# Periph.net
KiCad netlist of a schematic drawn in Altium Designer
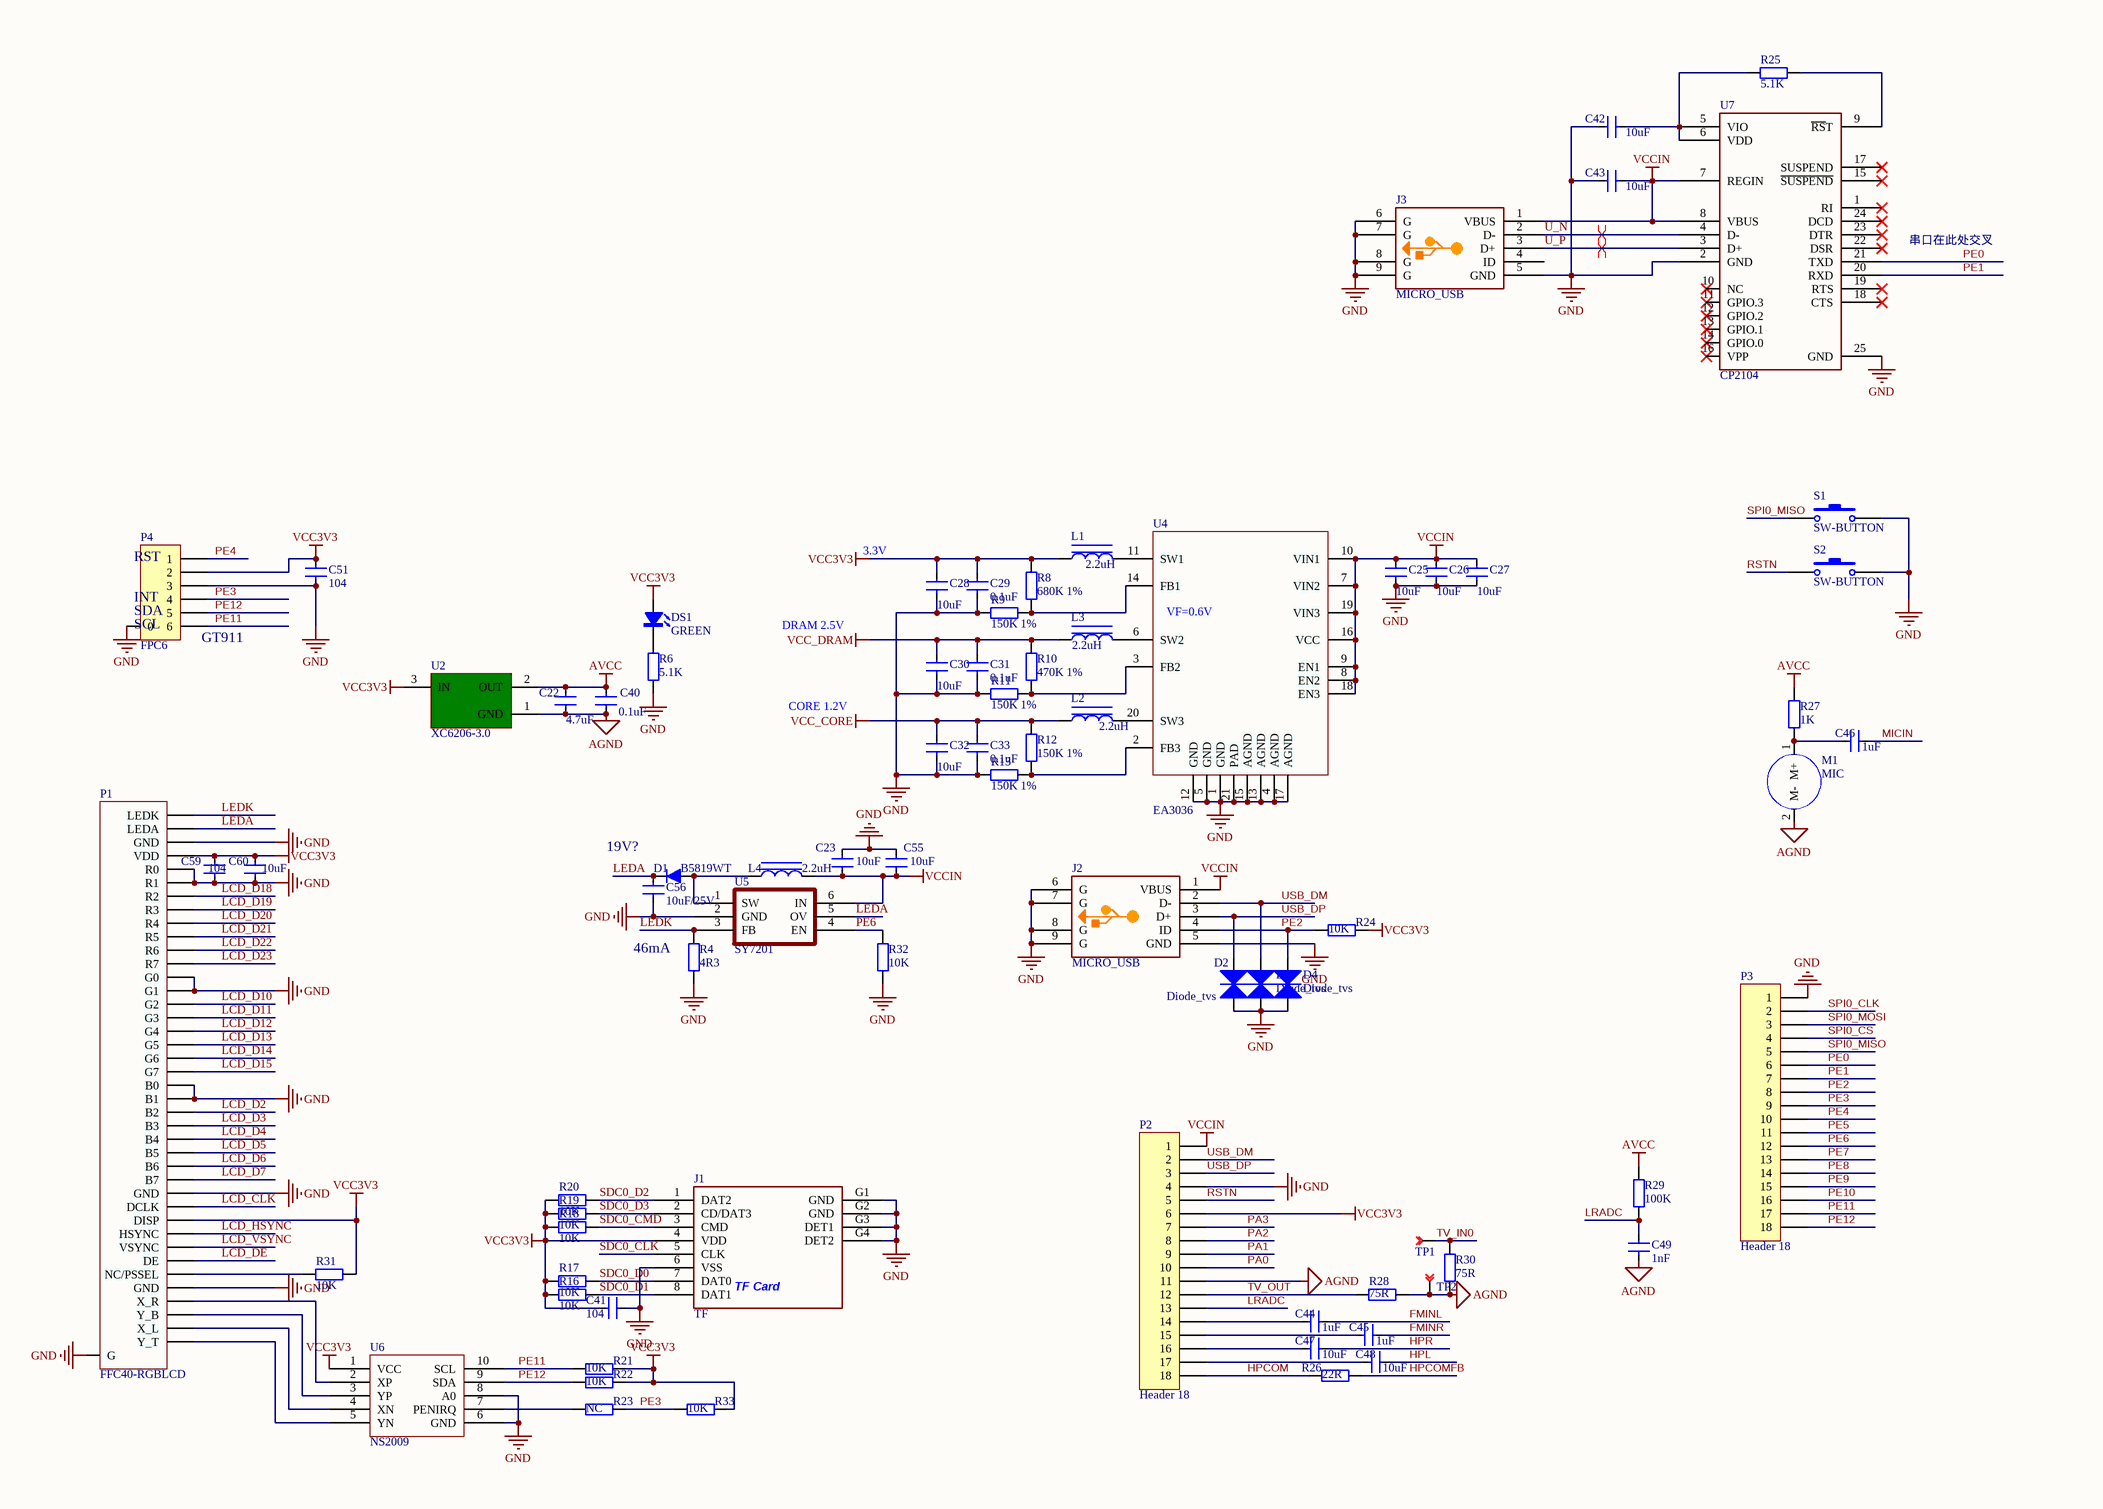
[diagram p0: Periph.SchDoc]

(export (version "E")
  (design (tool "Eeschema 10.0.6"))
  (components
    (comp (ref "C22")
      (value "4.7uF")
      (footprint "C0402")
      (description "普通小电容")
      (libsource (lib "LIB_MANGO") (part "CAP"))
    )
    (comp (ref "C23")
      (value "10uF")
      (footprint "C0402")
      (description "普通小电容")
      (libsource (lib "LIB_MANGO") (part "CAP"))
    )
    (comp (ref "C25")
      (value "10uF")
      (footprint "C0402")
      (description "普通小电容")
      (libsource (lib "LIB_MANGO") (part "CAP"))
    )
    (comp (ref "C26")
      (value "10uF")
      (footprint "C0402")
      (description "普通小电容")
      (libsource (lib "LIB_MANGO") (part "CAP"))
    )
    (comp (ref "C27")
      (value "10uF")
      (footprint "C0402")
      (description "普通小电容")
      (libsource (lib "LIB_MANGO") (part "CAP"))
    )
    (comp (ref "C28")
      (value "10uF")
      (footprint "C0402")
      (description "普通小电容")
      (libsource (lib "LIB_MANGO") (part "CAP"))
    )
    (comp (ref "C29")
      (value "0.1uF")
      (footprint "C0402")
      (description "普通小电容")
      (libsource (lib "LIB_MANGO") (part "CAP"))
    )
    (comp (ref "C30")
      (value "10uF")
      (footprint "C0402")
      (description "普通小电容")
      (libsource (lib "LIB_MANGO") (part "CAP"))
    )
    (comp (ref "C31")
      (value "0.1uF")
      (footprint "C0402")
      (description "普通小电容")
      (libsource (lib "LIB_MANGO") (part "CAP"))
    )
    (comp (ref "C32")
      (value "10uF")
      (footprint "C0402")
      (description "普通小电容")
      (libsource (lib "LIB_MANGO") (part "CAP"))
    )
    (comp (ref "C33")
      (value "0.1uF")
      (footprint "C0402")
      (description "普通小电容")
      (libsource (lib "LIB_MANGO") (part "CAP"))
    )
    (comp (ref "C40")
      (value "0.1uF")
      (footprint "C0402")
      (description "普通小电容")
      (libsource (lib "LIB_MANGO") (part "CAP"))
    )
    (comp (ref "C41")
      (value "104")
      (footprint "C0402")
      (description "普通小电容")
      (libsource (lib "LIB_MANGO") (part "CAP"))
    )
    (comp (ref "C42")
      (value "10uF")
      (footprint "C0402")
      (description "普通小电容")
      (libsource (lib "LIB_MANGO") (part "CAP"))
    )
    (comp (ref "C43")
      (value "10uF")
      (footprint "C0402")
      (description "普通小电容")
      (libsource (lib "LIB_MANGO") (part "CAP"))
    )
    (comp (ref "C44")
      (value "1uF")
      (footprint "C0402")
      (description "普通小电容")
      (libsource (lib "LIB_MANGO") (part "CAP"))
    )
    (comp (ref "C45")
      (value "1uF")
      (footprint "C0402")
      (description "普通小电容")
      (libsource (lib "LIB_MANGO") (part "CAP"))
    )
    (comp (ref "C46")
      (value "1uF")
      (footprint "C0402")
      (description "普通小电容")
      (libsource (lib "LIB_MANGO") (part "CAP"))
    )
    (comp (ref "C47")
      (value "10uF")
      (footprint "C0402")
      (description "普通小电容")
      (libsource (lib "LIB_MANGO") (part "CAP"))
    )
    (comp (ref "C48")
      (value "10uF")
      (footprint "C0402")
      (description "普通小电容")
      (libsource (lib "LIB_MANGO") (part "CAP"))
    )
    (comp (ref "C49")
      (value "1nF")
      (footprint "C0402")
      (description "普通小电容")
      (libsource (lib "LIB_MANGO") (part "CAP"))
    )
    (comp (ref "C51")
      (value "104")
      (footprint "C0402")
      (description "普通小电容")
      (libsource (lib "LIB_MANGO") (part "CAP"))
    )
    (comp (ref "C55")
      (value "10uF")
      (footprint "C0402")
      (description "普通小电容")
      (libsource (lib "LIB_MANGO") (part "CAP"))
    )
    (comp (ref "C56")
      (value "10uF/25V")
      (footprint "C0603")
      (description "普通小电容")
      (libsource (lib "LIB_MANGO") (part "CAP"))
    )
    (comp (ref "C59")
      (value "104")
      (footprint "C0402")
      (description "普通小电容")
      (libsource (lib "LIB_MANGO") (part "CAP"))
    )
    (comp (ref "C60")
      (value "10uF")
      (footprint "C0402")
      (description "普通小电容")
      (libsource (lib "LIB_MANGO") (part "CAP"))
    )
    (comp (ref "D1")
      (value "B5819WT")
      (footprint "SOD523")
      (description "普通二极管")
      (libsource (lib "A") (part "Diode"))
    )
    (comp (ref "D2")
      (value "Diode_tvs")
      (footprint "0402TVS")
      (description "tvs")
      (libsource (lib "LIB_MANGO") (part "Diode_tvs"))
    )
    (comp (ref "D3")
      (value "Diode_tvs")
      (footprint "0402TVS")
      (description "tvs")
      (libsource (lib "LIB_MANGO") (part "Diode_tvs"))
    )
    (comp (ref "D4")
      (value "Diode_tvs")
      (footprint "0402TVS")
      (description "tvs")
      (libsource (lib "LIB_MANGO") (part "Diode_tvs"))
    )
    (comp (ref "DS1") (value "GREEN") (footprint "LED0402") (libsource (lib "A") (part "LED")))
    (comp (ref "J1")
      (value "TF")
      (footprint "TFCARD473092651")
      (libsource (lib "LIB_MANGO") (part "TF_473092651"))
    )
    (comp (ref "J2")
      (value "MICRO_USB")
      (footprint "MICROUSB")
      (libsource (lib "LIB_MANGO") (part "MICRO_USB"))
    )
    (comp (ref "J3")
      (value "MICRO_USB")
      (footprint "MICROUSB")
      (libsource (lib "LIB_MANGO") (part "MICRO_USB"))
    )
    (comp (ref "L1")
      (value "2.2uH")
      (footprint "VLS2016")
      (description "普通电感")
      (libsource (lib "LIB_MANGO") (part "L"))
    )
    (comp (ref "L2")
      (value "2.2uH")
      (footprint "VLS2016")
      (description "普通电感")
      (libsource (lib "LIB_MANGO") (part "L"))
    )
    (comp (ref "L3")
      (value "2.2uH")
      (footprint "VLS2016")
      (description "普通电感")
      (libsource (lib "A") (part "L"))
    )
    (comp (ref "L4")
      (value "2.2uH")
      (footprint "VLS3012E")
      (description "普通电感")
      (libsource (lib "LIB_MANGO") (part "L"))
    )
    (comp (ref "M1") (value "MIC") (footprint "MIC") (libsource (lib "LIB_MANGO") (part "MIC")))
    (comp (ref "P1")
      (value "FFC40-RGBLCD")
      (footprint "FFC/SM0.5-1H40")
      (fields (field (name "PUBLISHER") "Altium Limited"))
      (libsource (lib "LIB_MANGO") (part "FFC40-RGBLCD"))
    )
    (comp (ref "P2")
      (value "Header 18")
      (footprint "HDR1X18-M2")
      (description "Header, 18-Pin")
      (fields (field (name "PUBLISHER") "Altium Limited"))
      (libsource (lib "LIB_MANGO") (part "Header 18"))
    )
    (comp (ref "P3")
      (value "Header 18")
      (footprint "HDR1X18-M2")
      (description "Header, 18-Pin")
      (fields (field (name "PUBLISHER") "Altium Limited"))
      (libsource (lib "LIB_MANGO") (part "Header 18"))
    )
    (comp (ref "P4")
      (value "FPC6")
      (footprint "FPC6")
      (fields (field (name "PUBLISHER") "Altium Limited"))
      (libsource (lib "LIB_MANGO") (part "FPC6"))
    )
    (comp (ref "R4")
      (value "4R3")
      (footprint "R0402")
      (description "普通电阻")
      (libsource (lib "") (part "RES_2"))
    )
    (comp (ref "R6")
      (value "5.1K")
      (footprint "R0402")
      (description "普通电阻1%精度")
      (libsource (lib "") (part "RES_1"))
    )
    (comp (ref "R8")
      (value "680K 1%")
      (footprint "R0402")
      (description "普通电阻")
      (libsource (lib "") (part "RES_1"))
    )
    (comp (ref "R9")
      (value "150K 1%")
      (footprint "R0402")
      (description "普通电阻")
      (libsource (lib "") (part "RES_3"))
    )
    (comp (ref "R10")
      (value "470K 1%")
      (footprint "R0402")
      (description "普通电阻")
      (libsource (lib "") (part "RES_1"))
    )
    (comp (ref "R11")
      (value "150K 1%")
      (footprint "R0402")
      (description "普通电阻")
      (libsource (lib "") (part "RES_3"))
    )
    (comp (ref "R12")
      (value "150K 1%")
      (footprint "R0402")
      (description "普通电阻")
      (libsource (lib "") (part "RES_1"))
    )
    (comp (ref "R13")
      (value "150K 1%")
      (footprint "R0402")
      (description "普通电阻")
      (libsource (lib "") (part "RES_3"))
    )
    (comp (ref "R16")
      (value "10K")
      (footprint "R0402")
      (description "普通电阻")
      (libsource (lib "") (part "RES_2"))
    )
    (comp (ref "R17")
      (value "10K")
      (footprint "R0402")
      (description "普通电阻")
      (libsource (lib "") (part "RES_2"))
    )
    (comp (ref "R18")
      (value "10K")
      (footprint "R0402")
      (description "普通电阻")
      (libsource (lib "") (part "RES_2"))
    )
    (comp (ref "R19")
      (value "10K")
      (footprint "R0402")
      (description "普通电阻")
      (libsource (lib "") (part "RES_2"))
    )
    (comp (ref "R20")
      (value "10K")
      (footprint "R0402")
      (description "普通电阻")
      (libsource (lib "") (part "RES_2"))
    )
    (comp (ref "R21")
      (value "10K")
      (footprint "R0402")
      (description "普通电阻")
      (libsource (lib "LIB_MANGO") (part "RES"))
    )
    (comp (ref "R22")
      (value "10K")
      (footprint "R0402")
      (description "普通电阻")
      (libsource (lib "LIB_MANGO") (part "RES"))
    )
    (comp (ref "R23")
      (value "NC")
      (footprint "R0402")
      (description "普通电阻")
      (libsource (lib "") (part "RES_2"))
    )
    (comp (ref "R24")
      (value "10K")
      (footprint "R0402")
      (description "普通电阻")
      (libsource (lib "LIB_MANGO") (part "RES"))
    )
    (comp (ref "R25")
      (value "5.1K")
      (footprint "R0402")
      (description "普通电阻")
      (libsource (lib "LIB_MANGO") (part "RES"))
    )
    (comp (ref "R26")
      (value "22R")
      (footprint "R0402")
      (description "普通电阻")
      (libsource (lib "LIB_MANGO") (part "RES"))
    )
    (comp (ref "R27")
      (value "1K")
      (footprint "R0402")
      (description "普通电阻")
      (libsource (lib "") (part "RES_1"))
    )
    (comp (ref "R28")
      (value "75R")
      (footprint "R0402")
      (description "普通电阻")
      (libsource (lib "LIB_MANGO") (part "RES"))
    )
    (comp (ref "R29")
      (value "100K")
      (footprint "R0402")
      (description "普通电阻")
      (libsource (lib "") (part "RES_2"))
    )
    (comp (ref "R30")
      (value "75R")
      (footprint "R0402")
      (description "普通电阻")
      (libsource (lib "") (part "RES_1"))
    )
    (comp (ref "R31")
      (value "10K")
      (footprint "R0402")
      (description "普通电阻")
      (libsource (lib "") (part "RES_3"))
    )
    (comp (ref "R32")
      (value "10K")
      (footprint "R0402")
      (description "普通电阻")
      (libsource (lib "") (part "RES_1"))
    )
    (comp (ref "R33")
      (value "10K")
      (footprint "R0402")
      (description "普通电阻")
      (libsource (lib "LIB_MANGO") (part "RES"))
    )
    (comp (ref "S1")
      (value "SW-BUTTON")
      (footprint "MINIBUTTON")
      (libsource (lib "LIB_MANGO") (part "SW-BUTTON"))
    )
    (comp (ref "S2")
      (value "SW-BUTTON")
      (footprint "MINIBUTTON")
      (libsource (lib "LIB_MANGO") (part "SW-BUTTON"))
    )
    (comp (ref "TP1")
      (value "TEST POINT")
      (footprint "TEST-POINT")
      (description "Description")
      (libsource (lib "LIB_MANGO") (part "TP"))
    )
    (comp (ref "TP2")
      (value "TEST POINT")
      (footprint "TEST-POINT")
      (description "Description")
      (libsource (lib "LIB_MANGO") (part "TP"))
    )
    (comp (ref "U2") (value "XC6206-3.0") (footprint "SOT23") (libsource (lib "LIB_MANGO") (part "XC6206")))
    (comp (ref "U4")
      (value "EA3036")
      (footprint "QFN40P300X300X80_HS-21N")
      (libsource (lib "LIB_MANGO") (part "EA3036"))
    )
    (comp (ref "U5") (value "SY7201") (footprint "SOT23-6") (libsource (lib "LIB_MANGO") (part "PT4101")))
    (comp (ref "U6") (value "NS2009") (footprint "TSSOP10") (libsource (lib "LIB_MANGO") (part "NS2009")))
    (comp (ref "U7") (value "CP2104") (footprint "QFN24") (libsource (lib "LIB_MANGO") (part "CP2104")))
  )
  (nets
    (net (code "1") (name "/FMINL") (class "Default")
      (node (ref "C44") (pin "2") (pinfunction "2_2") (pintype "passive"))
    )
    (net (code "2") (name "/FMINR") (class "Default")
      (node (ref "C45") (pin "2") (pinfunction "2_2") (pintype "passive"))
    )
    (net (code "3") (name "/HPCOM") (class "Default")
      (node (ref "P2") (pin "18") (pinfunction "18_18") (pintype "passive"))
      (node (ref "R26") (pin "1") (pinfunction "1_1") (pintype "passive"))
    )
    (net (code "4") (name "/HPCOMFB") (class "Default")
      (node (ref "R26") (pin "2") (pinfunction "2_2") (pintype "passive"))
    )
    (net (code "5") (name "/HPL") (class "Default")
      (node (ref "C48") (pin "2") (pinfunction "2_2") (pintype "passive"))
    )
    (net (code "6") (name "/HPR") (class "Default")
      (node (ref "C47") (pin "2") (pinfunction "2_2") (pintype "passive"))
    )
    (net (code "7") (name "/LCD_CLK") (class "Default")
      (node (ref "P1") (pin "30") (pinfunction "DCLK_30") (pintype "passive"))
    )
    (net (code "8") (name "/LCD_D2") (class "Default")
      (node (ref "P1") (pin "23") (pinfunction "B2_23") (pintype "passive"))
    )
    (net (code "9") (name "/LCD_D3") (class "Default")
      (node (ref "P1") (pin "24") (pinfunction "B3_24") (pintype "passive"))
    )
    (net (code "10") (name "/LCD_D4") (class "Default")
      (node (ref "P1") (pin "25") (pinfunction "B4_25") (pintype "passive"))
    )
    (net (code "11") (name "/LCD_D5") (class "Default")
      (node (ref "P1") (pin "26") (pinfunction "B5_26") (pintype "passive"))
    )
    (net (code "12") (name "/LCD_D6") (class "Default")
      (node (ref "P1") (pin "27") (pinfunction "B6_27") (pintype "passive"))
    )
    (net (code "13") (name "/LCD_D7") (class "Default")
      (node (ref "P1") (pin "28") (pinfunction "B7_28") (pintype "passive"))
    )
    (net (code "14") (name "/LCD_D10") (class "Default")
      (node (ref "P1") (pin "15") (pinfunction "G2_15") (pintype "passive"))
    )
    (net (code "15") (name "/LCD_D11") (class "Default")
      (node (ref "P1") (pin "16") (pinfunction "G3_16") (pintype "passive"))
    )
    (net (code "16") (name "/LCD_D12") (class "Default")
      (node (ref "P1") (pin "17") (pinfunction "G4_17") (pintype "passive"))
    )
    (net (code "17") (name "/LCD_D13") (class "Default")
      (node (ref "P1") (pin "18") (pinfunction "G5_18") (pintype "passive"))
    )
    (net (code "18") (name "/LCD_D14") (class "Default")
      (node (ref "P1") (pin "19") (pinfunction "G6_19") (pintype "passive"))
    )
    (net (code "19") (name "/LCD_D15") (class "Default")
      (node (ref "P1") (pin "20") (pinfunction "G7_20") (pintype "passive"))
    )
    (net (code "20") (name "/LCD_D18") (class "Default")
      (node (ref "P1") (pin "7") (pinfunction "R2_7") (pintype "passive"))
    )
    (net (code "21") (name "/LCD_D19") (class "Default")
      (node (ref "P1") (pin "8") (pinfunction "R3_8") (pintype "passive"))
    )
    (net (code "22") (name "/LCD_D20") (class "Default")
      (node (ref "P1") (pin "9") (pinfunction "R4_9") (pintype "passive"))
    )
    (net (code "23") (name "/LCD_D21") (class "Default")
      (node (ref "P1") (pin "10") (pinfunction "R5_10") (pintype "passive"))
    )
    (net (code "24") (name "/LCD_D22") (class "Default")
      (node (ref "P1") (pin "11") (pinfunction "R6_11") (pintype "passive"))
    )
    (net (code "25") (name "/LCD_D23") (class "Default")
      (node (ref "P1") (pin "12") (pinfunction "R7_12") (pintype "passive"))
    )
    (net (code "26") (name "/LCD_DE") (class "Default")
      (node (ref "P1") (pin "34") (pinfunction "DE_34") (pintype "passive"))
    )
    (net (code "27") (name "/LCD_HSYNC") (class "Default")
      (node (ref "P1") (pin "32") (pinfunction "HSYNC_32") (pintype "passive"))
    )
    (net (code "28") (name "/LCD_VSYNC") (class "Default")
      (node (ref "P1") (pin "33") (pinfunction "VSYNC_33") (pintype "passive"))
    )
    (net (code "29") (name "/LEDA") (class "Default")
      (node (ref "C56") (pin "2") (pinfunction "2_2") (pintype "passive"))
      (node (ref "D1") (pin "K") (pinfunction "K_K") (pintype "passive"))
      (node (ref "P1") (pin "2") (pinfunction "LEDA_2") (pintype "passive"))
      (node (ref "U5") (pin "5") (pinfunction "OV_5") (pintype "passive"))
    )
    (net (code "30") (name "/LEDK") (class "Default")
      (node (ref "P1") (pin "1") (pinfunction "LEDK_1") (pintype "passive"))
      (node (ref "R4") (pin "2") (pinfunction "2_2") (pintype "passive"))
      (node (ref "U5") (pin "3") (pinfunction "FB_3") (pintype "passive"))
    )
    (net (code "31") (name "/LRADC") (class "Default")
      (node (ref "C49") (pin "2") (pinfunction "2_2") (pintype "passive"))
      (node (ref "P2") (pin "13") (pinfunction "13_13") (pintype "passive"))
      (node (ref "R29") (pin "1") (pinfunction "1_1") (pintype "passive"))
    )
    (net (code "32") (name "/MICIN") (class "Default")
      (node (ref "C46") (pin "2") (pinfunction "2_2") (pintype "passive"))
    )
    (net (code "33") (name "/PA0") (class "Default")
      (node (ref "P2") (pin "10") (pinfunction "10_10") (pintype "passive"))
    )
    (net (code "34") (name "/PA1") (class "Default")
      (node (ref "P2") (pin "9") (pinfunction "9_9") (pintype "passive"))
    )
    (net (code "35") (name "/PA2") (class "Default")
      (node (ref "P2") (pin "8") (pinfunction "8_8") (pintype "passive"))
    )
    (net (code "36") (name "/PA3") (class "Default")
      (node (ref "P2") (pin "7") (pinfunction "7_7") (pintype "passive"))
    )
    (net (code "37") (name "/PE0") (class "Default")
      (node (ref "P3") (pin "6") (pinfunction "6_6") (pintype "passive"))
      (node (ref "U7") (pin "21") (pinfunction "TXD_21") (pintype "passive"))
    )
    (net (code "38") (name "/PE1") (class "Default")
      (node (ref "P3") (pin "7") (pinfunction "7_7") (pintype "passive"))
      (node (ref "U7") (pin "20") (pinfunction "RXD_20") (pintype "passive"))
    )
    (net (code "39") (name "/PE2") (class "Default")
      (node (ref "D4") (pin "2") (pinfunction "2_2") (pintype "passive"))
      (node (ref "J2") (pin "4") (pinfunction "ID_4") (pintype "passive"))
      (node (ref "P3") (pin "8") (pinfunction "8_8") (pintype "passive"))
      (node (ref "R24") (pin "1") (pinfunction "1_1") (pintype "passive"))
    )
    (net (code "40") (name "/PE3") (class "Default")
      (node (ref "P3") (pin "9") (pinfunction "9_9") (pintype "passive"))
      (node (ref "P4") (pin "4") (pinfunction "4_4") (pintype "passive"))
      (node (ref "R23") (pin "2") (pinfunction "2_2") (pintype "passive"))
      (node (ref "R33") (pin "1") (pinfunction "1_1") (pintype "passive"))
    )
    (net (code "41") (name "/PE4") (class "Default")
      (node (ref "P3") (pin "10") (pinfunction "10_10") (pintype "passive"))
      (node (ref "P4") (pin "1") (pinfunction "1_1") (pintype "passive"))
    )
    (net (code "42") (name "/PE5") (class "Default")
      (node (ref "P3") (pin "11") (pinfunction "11_11") (pintype "passive"))
    )
    (net (code "43") (name "/PE6") (class "Default")
      (node (ref "P3") (pin "12") (pinfunction "12_12") (pintype "passive"))
      (node (ref "R32") (pin "1") (pinfunction "1_1") (pintype "passive"))
      (node (ref "U5") (pin "4") (pinfunction "EN_4") (pintype "passive"))
    )
    (net (code "44") (name "/PE7") (class "Default")
      (node (ref "P3") (pin "13") (pinfunction "13_13") (pintype "passive"))
    )
    (net (code "45") (name "/PE8") (class "Default")
      (node (ref "P3") (pin "14") (pinfunction "14_14") (pintype "passive"))
    )
    (net (code "46") (name "/PE9") (class "Default")
      (node (ref "P3") (pin "15") (pinfunction "15_15") (pintype "passive"))
    )
    (net (code "47") (name "/PE10") (class "Default")
      (node (ref "P3") (pin "16") (pinfunction "16_16") (pintype "passive"))
    )
    (net (code "48") (name "/PE11") (class "Default")
      (node (ref "P3") (pin "17") (pinfunction "17_17") (pintype "passive"))
      (node (ref "P4") (pin "6") (pinfunction "6_6") (pintype "passive"))
      (node (ref "R21") (pin "1") (pinfunction "1_1") (pintype "passive"))
      (node (ref "U6") (pin "10") (pinfunction "SCL_10") (pintype "passive"))
    )
    (net (code "49") (name "/PE12") (class "Default")
      (node (ref "P3") (pin "18") (pinfunction "18_18") (pintype "passive"))
      (node (ref "P4") (pin "5") (pinfunction "5_5") (pintype "passive"))
      (node (ref "R22") (pin "1") (pinfunction "1_1") (pintype "passive"))
      (node (ref "U6") (pin "9") (pinfunction "SDA_9") (pintype "passive"))
    )
    (net (code "50") (name "/RSTN") (class "Default")
      (node (ref "P2") (pin "5") (pinfunction "5_5") (pintype "passive"))
      (node (ref "S2") (pin "1") (pinfunction "1_1") (pintype "passive"))
    )
    (net (code "51") (name "/SDC0_CLK") (class "Default")
      (node (ref "J1") (pin "5") (pinfunction "CLK_5") (pintype "passive"))
    )
    (net (code "52") (name "/SDC0_CMD") (class "Default")
      (node (ref "J1") (pin "3") (pinfunction "CMD_3") (pintype "passive"))
      (node (ref "R18") (pin "2") (pinfunction "2_2") (pintype "passive"))
    )
    (net (code "53") (name "/SDC0_D0") (class "Default")
      (node (ref "J1") (pin "7") (pinfunction "DAT0_7") (pintype "passive"))
      (node (ref "R17") (pin "2") (pinfunction "2_2") (pintype "passive"))
    )
    (net (code "54") (name "/SDC0_D1") (class "Default")
      (node (ref "J1") (pin "8") (pinfunction "DAT1_8") (pintype "passive"))
      (node (ref "R16") (pin "2") (pinfunction "2_2") (pintype "passive"))
    )
    (net (code "55") (name "/SDC0_D2") (class "Default")
      (node (ref "J1") (pin "1") (pinfunction "DAT2_1") (pintype "passive"))
      (node (ref "R20") (pin "2") (pinfunction "2_2") (pintype "passive"))
    )
    (net (code "56") (name "/SDC0_D3") (class "Default")
      (node (ref "J1") (pin "2") (pinfunction "CD/DAT3_2") (pintype "passive"))
      (node (ref "R19") (pin "2") (pinfunction "2_2") (pintype "passive"))
    )
    (net (code "57") (name "/SPI0_CLK") (class "Default")
      (node (ref "P3") (pin "2") (pinfunction "2_2") (pintype "passive"))
    )
    (net (code "58") (name "/SPI0_CS") (class "Default")
      (node (ref "P3") (pin "4") (pinfunction "4_4") (pintype "passive"))
    )
    (net (code "59") (name "/SPI0_MISO") (class "Default")
      (node (ref "P3") (pin "5") (pinfunction "5_5") (pintype "passive"))
      (node (ref "S1") (pin "1") (pinfunction "1_1") (pintype "passive"))
    )
    (net (code "60") (name "/SPI0_MOSI") (class "Default")
      (node (ref "P3") (pin "3") (pinfunction "3_3") (pintype "passive"))
    )
    (net (code "61") (name "/TV_IN0") (class "Default")
      (node (ref "R30") (pin "1") (pinfunction "1_1") (pintype "passive"))
      (node (ref "TP1") (pin "1") (pinfunction "1_1") (pintype "passive"))
    )
    (net (code "62") (name "/TV_OUT") (class "Default")
      (node (ref "P2") (pin "12") (pinfunction "12_12") (pintype "passive"))
      (node (ref "R28") (pin "1") (pinfunction "1_1") (pintype "passive"))
    )
    (net (code "63") (name "/USB_DM") (class "Default")
      (node (ref "D3") (pin "2") (pinfunction "2_2") (pintype "passive"))
      (node (ref "J2") (pin "2") (pinfunction "D-_2") (pintype "passive"))
      (node (ref "P2") (pin "2") (pinfunction "2_2") (pintype "passive"))
    )
    (net (code "64") (name "/USB_DP") (class "Default")
      (node (ref "D2") (pin "1") (pinfunction "1_1") (pintype "passive"))
      (node (ref "J2") (pin "3") (pinfunction "D+_3") (pintype "passive"))
      (node (ref "P2") (pin "3") (pinfunction "3_3") (pintype "passive"))
    )
    (net (code "65") (name "/U_N") (class "Default")
      (node (ref "J3") (pin "2") (pinfunction "D-_2") (pintype "passive"))
      (node (ref "U7") (pin "4") (pinfunction "D-_4") (pintype "passive"))
    )
    (net (code "66") (name "/U_P") (class "Default")
      (node (ref "J3") (pin "3") (pinfunction "D+_3") (pintype "passive"))
      (node (ref "U7") (pin "3") (pinfunction "D+_3") (pintype "passive"))
    )
    (net (code "67") (name "AGND") (class "Default")
      (node (ref "C22") (pin "1") (pinfunction "1_1") (pintype "passive"))
      (node (ref "C40") (pin "1") (pinfunction "1_1") (pintype "passive"))
      (node (ref "C49") (pin "1") (pinfunction "1_1") (pintype "passive"))
      (node (ref "M1") (pin "2") (pinfunction "M-_2") (pintype "passive"))
      (node (ref "P2") (pin "11") (pinfunction "11_11") (pintype "passive"))
      (node (ref "R28") (pin "2") (pinfunction "2_2") (pintype "passive"))
      (node (ref "R30") (pin "2") (pinfunction "2_2") (pintype "passive"))
      (node (ref "TP2") (pin "1") (pinfunction "1_1") (pintype "passive"))
      (node (ref "U2") (pin "1") (pinfunction "GND_1") (pintype "passive"))
    )
    (net (code "68") (name "AVCC") (class "Default")
      (node (ref "C22") (pin "2") (pinfunction "2_2") (pintype "passive"))
      (node (ref "C40") (pin "2") (pinfunction "2_2") (pintype "passive"))
      (node (ref "R27") (pin "1") (pinfunction "1_1") (pintype "passive"))
      (node (ref "R29") (pin "2") (pinfunction "2_2") (pintype "passive"))
      (node (ref "U2") (pin "2") (pinfunction "OUT_2") (pintype "passive"))
    )
    (net (code "69") (name "GND") (class "Default")
      (node (ref "C23") (pin "2") (pinfunction "2_2") (pintype "passive"))
      (node (ref "C25") (pin "2") (pinfunction "2_2") (pintype "passive"))
      (node (ref "C26") (pin "2") (pinfunction "2_2") (pintype "passive"))
      (node (ref "C27") (pin "2") (pinfunction "2_2") (pintype "passive"))
      (node (ref "C28") (pin "2") (pinfunction "2_2") (pintype "passive"))
      (node (ref "C29") (pin "1") (pinfunction "1_1") (pintype "passive"))
      (node (ref "C30") (pin "2") (pinfunction "2_2") (pintype "passive"))
      (node (ref "C31") (pin "1") (pinfunction "1_1") (pintype "passive"))
      (node (ref "C32") (pin "2") (pinfunction "2_2") (pintype "passive"))
      (node (ref "C33") (pin "1") (pinfunction "1_1") (pintype "passive"))
      (node (ref "C41") (pin "2") (pinfunction "2_2") (pintype "passive"))
      (node (ref "C42") (pin "2") (pinfunction "2_2") (pintype "passive"))
      (node (ref "C43") (pin "1") (pinfunction "1_1") (pintype "passive"))
      (node (ref "C51") (pin "1") (pinfunction "1_1") (pintype "passive"))
      (node (ref "C55") (pin "1") (pinfunction "1_1") (pintype "passive"))
      (node (ref "C56") (pin "1") (pinfunction "1_1") (pintype "passive"))
      (node (ref "C59") (pin "2") (pinfunction "2_2") (pintype "passive"))
      (node (ref "C60") (pin "1") (pinfunction "1_1") (pintype "passive"))
      (node (ref "D2") (pin "2") (pinfunction "2_2") (pintype "passive"))
      (node (ref "D3") (pin "1") (pinfunction "1_1") (pintype "passive"))
      (node (ref "D4") (pin "1") (pinfunction "1_1") (pintype "passive"))
      (node (ref "J1") (pin "6") (pinfunction "VSS_6") (pintype "power_in"))
      (node (ref "J1") (pin "G1") (pinfunction "GND_G1") (pintype "power_in"))
      (node (ref "J1") (pin "G2") (pinfunction "GND_G2") (pintype "power_in"))
      (node (ref "J1") (pin "G3") (pinfunction "DET1_G3") (pintype "power_in"))
      (node (ref "J1") (pin "G4") (pinfunction "DET2_G4") (pintype "power_in"))
      (node (ref "J2") (pin "5") (pinfunction "GND_5") (pintype "power_in"))
      (node (ref "J2") (pin "6") (pinfunction "G_6") (pintype "passive"))
      (node (ref "J2") (pin "7") (pinfunction "G_7") (pintype "passive"))
      (node (ref "J2") (pin "8") (pinfunction "G_8") (pintype "passive"))
      (node (ref "J2") (pin "9") (pinfunction "G_9") (pintype "passive"))
      (node (ref "J3") (pin "5") (pinfunction "GND_5") (pintype "power_in"))
      (node (ref "J3") (pin "6") (pinfunction "G_6") (pintype "passive"))
      (node (ref "J3") (pin "7") (pinfunction "G_7") (pintype "passive"))
      (node (ref "J3") (pin "8") (pinfunction "G_8") (pintype "passive"))
      (node (ref "J3") (pin "9") (pinfunction "G_9") (pintype "passive"))
      (node (ref "P1") (pin "13") (pinfunction "G0_13") (pintype "passive"))
      (node (ref "P1") (pin "14") (pinfunction "G1_14") (pintype "passive"))
      (node (ref "P1") (pin "21") (pinfunction "B0_21") (pintype "passive"))
      (node (ref "P1") (pin "22") (pinfunction "B1_22") (pintype "passive"))
      (node (ref "P1") (pin "29") (pinfunction "GND_29") (pintype "passive"))
      (node (ref "P1") (pin "3") (pinfunction "GND_3") (pintype "passive"))
      (node (ref "P1") (pin "36") (pinfunction "GND_36") (pintype "passive"))
      (node (ref "P1") (pin "5") (pinfunction "R0_5") (pintype "passive"))
      (node (ref "P1") (pin "6") (pinfunction "R1_6") (pintype "passive"))
      (node (ref "P1") (pin "G") (pinfunction "G_G") (pintype "passive"))
      (node (ref "P2") (pin "4") (pinfunction "4_4") (pintype "passive"))
      (node (ref "P3") (pin "1") (pinfunction "1_1") (pintype "passive"))
      (node (ref "P4") (pin "0") (pinfunction "0_0") (pintype "passive"))
      (node (ref "P4") (pin "3") (pinfunction "3_3") (pintype "passive"))
      (node (ref "R11") (pin "2") (pinfunction "2_2") (pintype "passive"))
      (node (ref "R13") (pin "2") (pinfunction "2_2") (pintype "passive"))
      (node (ref "R32") (pin "2") (pinfunction "2_2") (pintype "passive"))
      (node (ref "R4") (pin "1") (pinfunction "1_1") (pintype "passive"))
      (node (ref "R6") (pin "2") (pinfunction "2_2") (pintype "passive"))
      (node (ref "R9") (pin "2") (pinfunction "2_2") (pintype "passive"))
      (node (ref "S1") (pin "2") (pinfunction "2_2") (pintype "passive"))
      (node (ref "S2") (pin "2") (pinfunction "2_2") (pintype "passive"))
      (node (ref "U4") (pin "1") (pinfunction "GND_1") (pintype "passive"))
      (node (ref "U4") (pin "12") (pinfunction "GND_12") (pintype "passive"))
      (node (ref "U4") (pin "13") (pinfunction "AGND_13") (pintype "passive"))
      (node (ref "U4") (pin "15") (pinfunction "AGND_15") (pintype "passive"))
      (node (ref "U4") (pin "17") (pinfunction "AGND_17") (pintype "passive"))
      (node (ref "U4") (pin "21") (pinfunction "PAD_21") (pintype "passive"))
      (node (ref "U4") (pin "4") (pinfunction "AGND_4") (pintype "passive"))
      (node (ref "U4") (pin "5") (pinfunction "GND_5") (pintype "passive"))
      (node (ref "U5") (pin "2") (pinfunction "GND_2") (pintype "passive"))
      (node (ref "U6") (pin "6") (pinfunction "GND_6") (pintype "passive"))
      (node (ref "U6") (pin "8") (pinfunction "A0_8") (pintype "passive"))
      (node (ref "U7") (pin "2") (pinfunction "GND_2") (pintype "power_in"))
      (node (ref "U7") (pin "25") (pinfunction "GND_25") (pintype "power_in"))
    )
    (net (code "70") (name "Net-(C44-Pad1)") (class "Default")
      (node (ref "C44") (pin "1") (pinfunction "1_1") (pintype "passive"))
      (node (ref "P2") (pin "14") (pinfunction "14_14") (pintype "passive"))
    )
    (net (code "71") (name "Net-(C45-Pad1)") (class "Default")
      (node (ref "C45") (pin "1") (pinfunction "1_1") (pintype "passive"))
      (node (ref "P2") (pin "15") (pinfunction "15_15") (pintype "passive"))
    )
    (net (code "72") (name "Net-(C47-Pad1)") (class "Default")
      (node (ref "C47") (pin "1") (pinfunction "1_1") (pintype "passive"))
      (node (ref "P2") (pin "16") (pinfunction "16_16") (pintype "passive"))
    )
    (net (code "73") (name "Net-(C48-Pad1)") (class "Default")
      (node (ref "C48") (pin "1") (pinfunction "1_1") (pintype "passive"))
      (node (ref "P2") (pin "17") (pinfunction "17_17") (pintype "passive"))
    )
    (net (code "74") (name "Net-(DS1-2)") (class "Default")
      (node (ref "DS1") (pin "K") (pinfunction "2_K") (pintype "passive"))
      (node (ref "R6") (pin "1") (pinfunction "1_1") (pintype "passive"))
    )
    (net (code "75") (name "Net-(M1-M+)") (class "Default")
      (node (ref "C46") (pin "1") (pinfunction "1_1") (pintype "passive"))
      (node (ref "M1") (pin "1") (pinfunction "M+_1") (pintype "passive"))
      (node (ref "R27") (pin "2") (pinfunction "2_2") (pintype "passive"))
    )
    (net (code "76") (name "Net-(P1-NC{slash}PSSEL)") (class "Default")
      (node (ref "P1") (pin "35") (pinfunction "NC/PSSEL_35") (pintype "passive"))
      (node (ref "R31") (pin "2") (pinfunction "2_2") (pintype "passive"))
    )
    (net (code "77") (name "Net-(P1-X_L)") (class "Default")
      (node (ref "P1") (pin "39") (pinfunction "X_L_39") (pintype "passive"))
      (node (ref "U6") (pin "4") (pinfunction "XN_4") (pintype "passive"))
    )
    (net (code "78") (name "Net-(P1-X_R)") (class "Default")
      (node (ref "P1") (pin "37") (pinfunction "X_R_37") (pintype "passive"))
      (node (ref "U6") (pin "2") (pinfunction "XP_2") (pintype "passive"))
    )
    (net (code "79") (name "Net-(P1-Y_B)") (class "Default")
      (node (ref "P1") (pin "38") (pinfunction "Y_B_38") (pintype "passive"))
      (node (ref "U6") (pin "3") (pinfunction "YP_3") (pintype "passive"))
    )
    (net (code "80") (name "Net-(P1-Y_T)") (class "Default")
      (node (ref "P1") (pin "40") (pinfunction "Y_T_40") (pintype "passive"))
      (node (ref "U6") (pin "5") (pinfunction "YN_5") (pintype "passive"))
    )
    (net (code "81") (name "Net-(U4-FB1)") (class "Default")
      (node (ref "R8") (pin "2") (pinfunction "2_2") (pintype "passive"))
      (node (ref "R9") (pin "1") (pinfunction "1_1") (pintype "passive"))
      (node (ref "U4") (pin "14") (pinfunction "FB1_14") (pintype "passive"))
    )
    (net (code "82") (name "Net-(U4-FB2)") (class "Default")
      (node (ref "R10") (pin "2") (pinfunction "2_2") (pintype "passive"))
      (node (ref "R11") (pin "1") (pinfunction "1_1") (pintype "passive"))
      (node (ref "U4") (pin "3") (pinfunction "FB2_3") (pintype "passive"))
    )
    (net (code "83") (name "Net-(U4-FB3)") (class "Default")
      (node (ref "R12") (pin "2") (pinfunction "2_2") (pintype "passive"))
      (node (ref "R13") (pin "1") (pinfunction "1_1") (pintype "passive"))
      (node (ref "U4") (pin "2") (pinfunction "FB3_2") (pintype "passive"))
    )
    (net (code "84") (name "Net-(U4-SW1)") (class "Default")
      (node (ref "L1") (pin "1") (pinfunction "1_1") (pintype "passive"))
      (node (ref "U4") (pin "11") (pinfunction "SW1_11") (pintype "passive"))
    )
    (net (code "85") (name "Net-(U4-SW2)") (class "Default")
      (node (ref "L3") (pin "1") (pinfunction "1_1") (pintype "passive"))
      (node (ref "U4") (pin "6") (pinfunction "SW2_6") (pintype "passive"))
    )
    (net (code "86") (name "Net-(U4-SW3)") (class "Default")
      (node (ref "L2") (pin "1") (pinfunction "1_1") (pintype "passive"))
      (node (ref "U4") (pin "20") (pinfunction "SW3_20") (pintype "passive"))
    )
    (net (code "87") (name "Net-(U5-SW)") (class "Default")
      (node (ref "D1") (pin "A") (pinfunction "A_A") (pintype "passive"))
      (node (ref "L4") (pin "2") (pinfunction "2_2") (pintype "passive"))
      (node (ref "U5") (pin "1") (pinfunction "SW_1") (pintype "passive"))
    )
    (net (code "88") (name "Net-(U6-PENIRQ)") (class "Default")
      (node (ref "R23") (pin "1") (pinfunction "1_1") (pintype "passive"))
      (node (ref "U6") (pin "7") (pinfunction "PENIRQ_7") (pintype "passive"))
    )
    (net (code "89") (name "Net-(U7-VDD)") (class "Default")
      (node (ref "C42") (pin "1") (pinfunction "1_1") (pintype "passive"))
      (node (ref "R25") (pin "1") (pinfunction "1_1") (pintype "passive"))
      (node (ref "U7") (pin "5") (pinfunction "VIO_5") (pintype "passive"))
      (node (ref "U7") (pin "6") (pinfunction "VDD_6") (pintype "passive"))
    )
    (net (code "90") (name "Net-(U7-~{RS}T)") (class "Default")
      (node (ref "R25") (pin "2") (pinfunction "2_2") (pintype "passive"))
      (node (ref "U7") (pin "9") (pinfunction "~{RS}T_9") (pintype "passive"))
    )
    (net (code "91") (name "VCC3V3") (class "Default")
      (node (ref "C28") (pin "1") (pinfunction "1_1") (pintype "passive"))
      (node (ref "C29") (pin "2") (pinfunction "2_2") (pintype "passive"))
      (node (ref "C41") (pin "1") (pinfunction "1_1") (pintype "passive"))
      (node (ref "C51") (pin "2") (pinfunction "2_2") (pintype "passive"))
      (node (ref "C59") (pin "1") (pinfunction "1_1") (pintype "passive"))
      (node (ref "C60") (pin "2") (pinfunction "2_2") (pintype "passive"))
      (node (ref "DS1") (pin "A") (pinfunction "1_A") (pintype "passive"))
      (node (ref "J1") (pin "4") (pinfunction "VDD_4") (pintype "power_in"))
      (node (ref "L1") (pin "2") (pinfunction "2_2") (pintype "passive"))
      (node (ref "P1") (pin "31") (pinfunction "DISP_31") (pintype "passive"))
      (node (ref "P1") (pin "4") (pinfunction "VDD_4") (pintype "passive"))
      (node (ref "P2") (pin "6") (pinfunction "6_6") (pintype "passive"))
      (node (ref "P4") (pin "2") (pinfunction "2_2") (pintype "passive"))
      (node (ref "R16") (pin "1") (pinfunction "1_1") (pintype "passive"))
      (node (ref "R17") (pin "1") (pinfunction "1_1") (pintype "passive"))
      (node (ref "R18") (pin "1") (pinfunction "1_1") (pintype "passive"))
      (node (ref "R19") (pin "1") (pinfunction "1_1") (pintype "passive"))
      (node (ref "R20") (pin "1") (pinfunction "1_1") (pintype "passive"))
      (node (ref "R21") (pin "2") (pinfunction "2_2") (pintype "passive"))
      (node (ref "R22") (pin "2") (pinfunction "2_2") (pintype "passive"))
      (node (ref "R24") (pin "2") (pinfunction "2_2") (pintype "passive"))
      (node (ref "R31") (pin "1") (pinfunction "1_1") (pintype "passive"))
      (node (ref "R33") (pin "2") (pinfunction "2_2") (pintype "passive"))
      (node (ref "R8") (pin "1") (pinfunction "1_1") (pintype "passive"))
      (node (ref "U2") (pin "3") (pinfunction "IN_3") (pintype "passive"))
      (node (ref "U6") (pin "1") (pinfunction "VCC_1") (pintype "passive"))
    )
    (net (code "92") (name "VCCIN") (class "Default")
      (node (ref "C23") (pin "1") (pinfunction "1_1") (pintype "passive"))
      (node (ref "C25") (pin "1") (pinfunction "1_1") (pintype "passive"))
      (node (ref "C26") (pin "1") (pinfunction "1_1") (pintype "passive"))
      (node (ref "C27") (pin "1") (pinfunction "1_1") (pintype "passive"))
      (node (ref "C43") (pin "2") (pinfunction "2_2") (pintype "passive"))
      (node (ref "C55") (pin "2") (pinfunction "2_2") (pintype "passive"))
      (node (ref "J2") (pin "1") (pinfunction "VBUS_1") (pintype "power_in"))
      (node (ref "J3") (pin "1") (pinfunction "VBUS_1") (pintype "power_in"))
      (node (ref "L4") (pin "1") (pinfunction "1_1") (pintype "passive"))
      (node (ref "P2") (pin "1") (pinfunction "1_1") (pintype "passive"))
      (node (ref "U4") (pin "10") (pinfunction "VIN1_10") (pintype "passive"))
      (node (ref "U4") (pin "16") (pinfunction "VCC_16") (pintype "passive"))
      (node (ref "U4") (pin "18") (pinfunction "EN3_18") (pintype "passive"))
      (node (ref "U4") (pin "19") (pinfunction "VIN3_19") (pintype "passive"))
      (node (ref "U4") (pin "7") (pinfunction "VIN2_7") (pintype "passive"))
      (node (ref "U4") (pin "8") (pinfunction "EN2_8") (pintype "passive"))
      (node (ref "U4") (pin "9") (pinfunction "EN1_9") (pintype "passive"))
      (node (ref "U5") (pin "6") (pinfunction "IN_6") (pintype "passive"))
      (node (ref "U7") (pin "7") (pinfunction "REGIN_7") (pintype "passive"))
      (node (ref "U7") (pin "8") (pinfunction "VBUS_8") (pintype "power_in"))
    )
    (net (code "93") (name "VCC_CORE") (class "Default")
      (node (ref "C32") (pin "1") (pinfunction "1_1") (pintype "passive"))
      (node (ref "C33") (pin "2") (pinfunction "2_2") (pintype "passive"))
      (node (ref "L2") (pin "2") (pinfunction "2_2") (pintype "passive"))
      (node (ref "R12") (pin "1") (pinfunction "1_1") (pintype "passive"))
    )
    (net (code "94") (name "VCC_DRAM") (class "Default")
      (node (ref "C30") (pin "1") (pinfunction "1_1") (pintype "passive"))
      (node (ref "C31") (pin "2") (pinfunction "2_2") (pintype "passive"))
      (node (ref "L3") (pin "2") (pinfunction "2_2") (pintype "passive"))
      (node (ref "R10") (pin "1") (pinfunction "1_1") (pintype "passive"))
    )
    (net (code "95") (name "unconnected-(J3-ID-Pad4)") (class "Default")
      (node (ref "J3") (pin "4") (pinfunction "ID_4") (pintype "passive"))
    )
    (net (code "96") (name "unconnected-(U7-CTS-Pad18)") (class "Default")
      (node (ref "U7") (pin "18") (pinfunction "CTS_18") (pintype "passive+no_connect"))
    )
    (net (code "97") (name "unconnected-(U7-DCD-Pad24)") (class "Default")
      (node (ref "U7") (pin "24") (pinfunction "DCD_24") (pintype "passive+no_connect"))
    )
    (net (code "98") (name "unconnected-(U7-DSR-Pad22)") (class "Default")
      (node (ref "U7") (pin "22") (pinfunction "DSR_22") (pintype "passive+no_connect"))
    )
    (net (code "99") (name "unconnected-(U7-DTR-Pad23)") (class "Default")
      (node (ref "U7") (pin "23") (pinfunction "DTR_23") (pintype "passive+no_connect"))
    )
    (net (code "100") (name "unconnected-(U7-GPIO.0-Pad14)") (class "Default")
      (node (ref "U7") (pin "14") (pinfunction "GPIO.0_14") (pintype "passive+no_connect"))
    )
    (net (code "101") (name "unconnected-(U7-GPIO.1-Pad13)") (class "Default")
      (node (ref "U7") (pin "13") (pinfunction "GPIO.1_13") (pintype "passive+no_connect"))
    )
    (net (code "102") (name "unconnected-(U7-GPIO.2-Pad12)") (class "Default")
      (node (ref "U7") (pin "12") (pinfunction "GPIO.2_12") (pintype "passive+no_connect"))
    )
    (net (code "103") (name "unconnected-(U7-GPIO.3-Pad11)") (class "Default")
      (node (ref "U7") (pin "11") (pinfunction "GPIO.3_11") (pintype "passive+no_connect"))
    )
    (net (code "104") (name "unconnected-(U7-NC-Pad10)") (class "Default")
      (node (ref "U7") (pin "10") (pinfunction "NC_10") (pintype "passive+no_connect"))
    )
    (net (code "105") (name "unconnected-(U7-RI-Pad1)") (class "Default")
      (node (ref "U7") (pin "1") (pinfunction "RI_1") (pintype "passive+no_connect"))
    )
    (net (code "106") (name "unconnected-(U7-RTS-Pad19)") (class "Default")
      (node (ref "U7") (pin "19") (pinfunction "RTS_19") (pintype "passive+no_connect"))
    )
    (net (code "107") (name "unconnected-(U7-SUSPEND-Pad17)") (class "Default")
      (node (ref "U7") (pin "17") (pinfunction "SUSPEND_17") (pintype "passive+no_connect"))
    )
    (net (code "108") (name "unconnected-(U7-VPP-Pad16)") (class "Default")
      (node (ref "U7") (pin "16") (pinfunction "VPP_16") (pintype "passive+no_connect"))
    )
    (net (code "109") (name "unconnected-(U7-~{SUSPEND}-Pad15)") (class "Default")
      (node (ref "U7") (pin "15") (pinfunction "~{SUSPEND}_15") (pintype "passive+no_connect"))
    )
  )
)
